# amp_soha.net
KiCad netlist of a schematic drawn in EAGLE
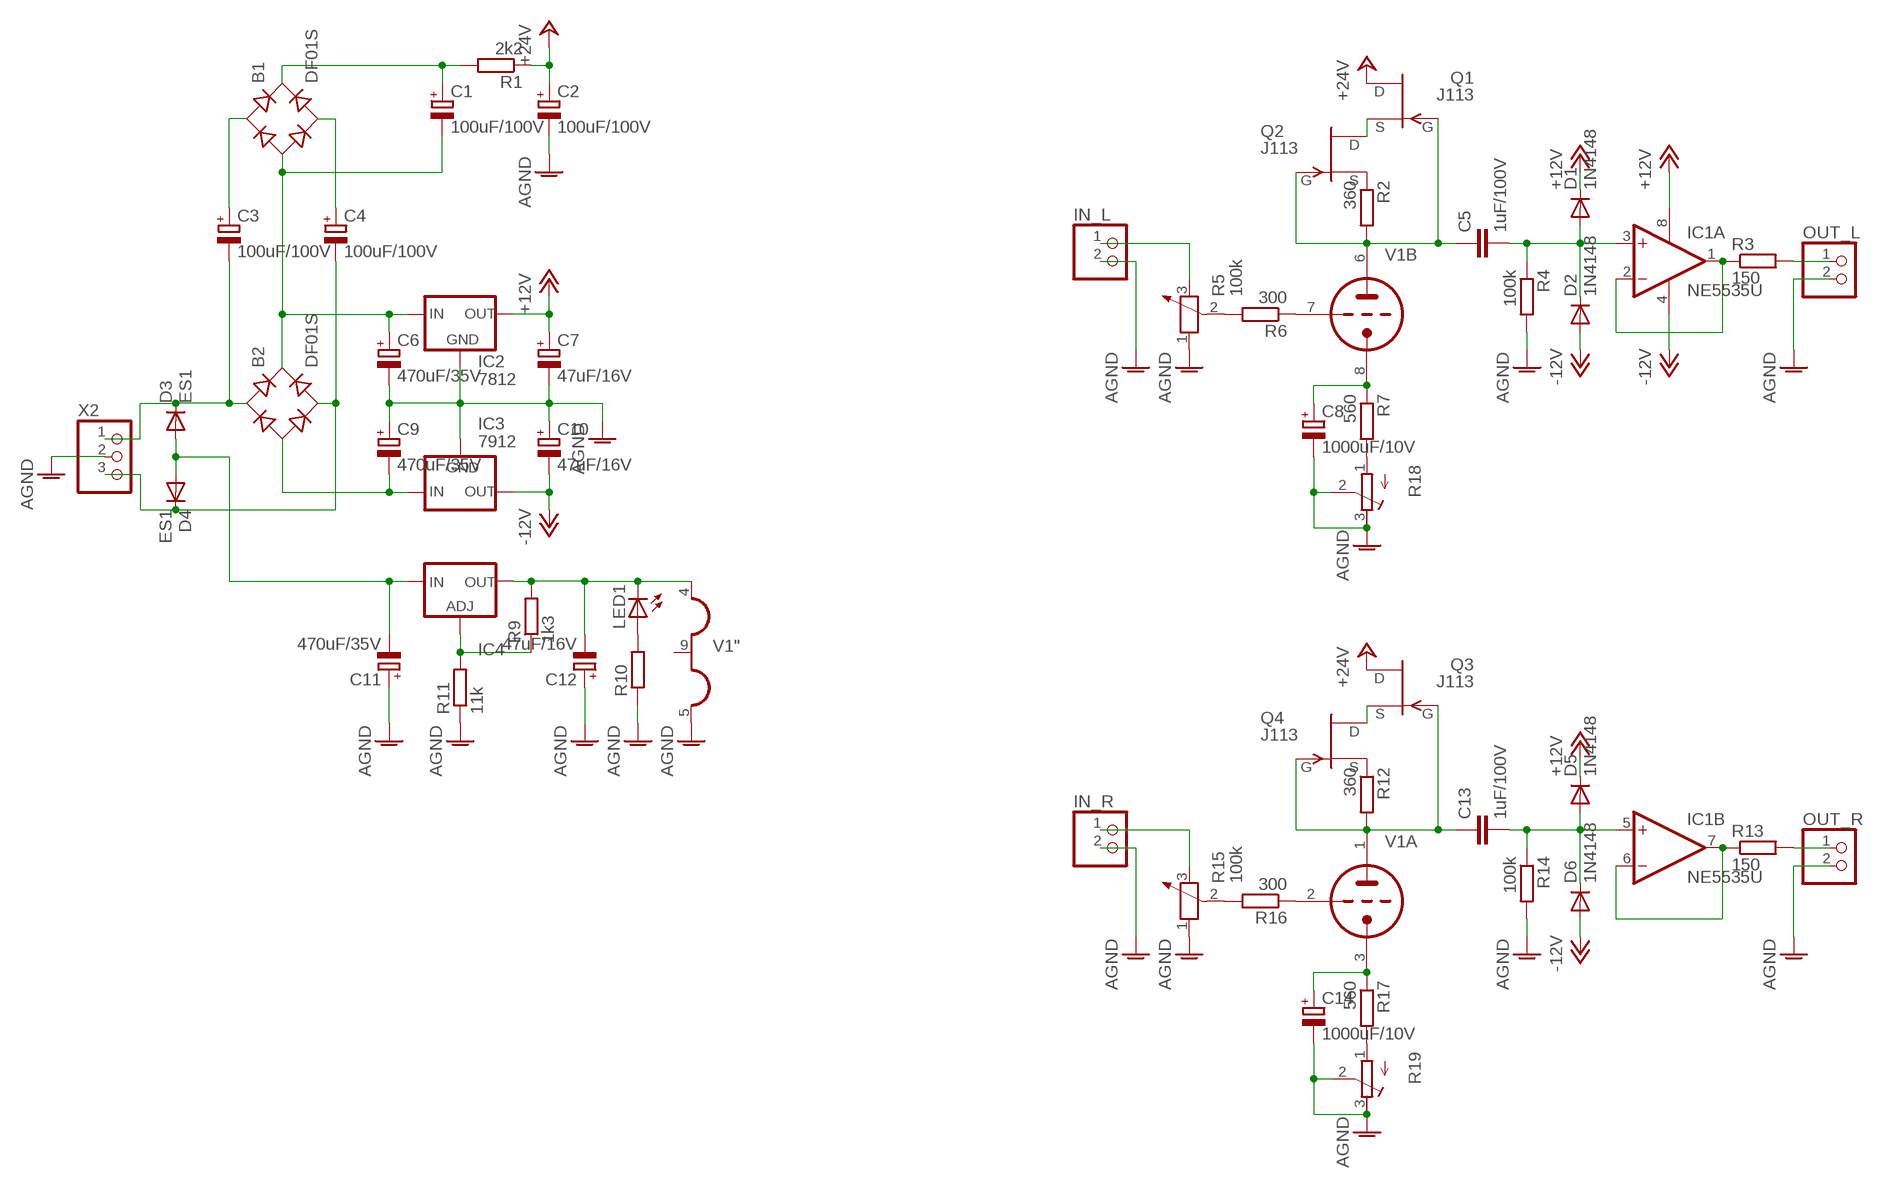
[diagram p0: schematic, sheet 1]

(export (version "E")
  (design (tool "Eeschema 10.0.6"))
  (components
    (comp (ref "B1")
      (value "DF01S")
      (footprint "eagle-import:DFS")
      (libsource (lib "eagle-import") (part "DFS01"))
    )
    (comp (ref "B2")
      (value "DF01S")
      (footprint "eagle-import:DFS")
      (libsource (lib "eagle-import") (part "DFS01"))
    )
    (comp (ref "C1")
      (value "100uF/100V")
      (footprint "eagle-import:E5-10,5")
      (libsource (lib "eagle-import") (part "CPOL-EUE5-10,5"))
    )
    (comp (ref "C2")
      (value "100uF/100V")
      (footprint "eagle-import:E5-10,5")
      (libsource (lib "eagle-import") (part "CPOL-EUE5-10,5"))
    )
    (comp (ref "C3")
      (value "100uF/100V")
      (footprint "eagle-import:E5-10,5")
      (libsource (lib "eagle-import") (part "CPOL-EUE5-10,5"))
    )
    (comp (ref "C4")
      (value "100uF/100V")
      (footprint "eagle-import:E5-10,5")
      (libsource (lib "eagle-import") (part "CPOL-EUE5-10,5"))
    )
    (comp (ref "C5")
      (value "1uF/100V")
      (footprint "eagle-import:C150-072X183")
      (libsource (lib "eagle-import") (part "C-EU150-072X183"))
    )
    (comp (ref "C6")
      (value "470uF/35V")
      (footprint "eagle-import:E5-10,5")
      (libsource (lib "eagle-import") (part "CPOL-EUE5-10,5"))
    )
    (comp (ref "C7")
      (value "47uF/16V")
      (footprint "eagle-import:E2,5-6")
      (libsource (lib "eagle-import") (part "CPOL-EUE2.5-6"))
    )
    (comp (ref "C8")
      (value "1000uF/10V")
      (footprint "eagle-import:E5-10,5")
      (libsource (lib "eagle-import") (part "CPOL-EUE5-10,5"))
    )
    (comp (ref "C9")
      (value "470uF/35V")
      (footprint "eagle-import:E5-10,5")
      (libsource (lib "eagle-import") (part "CPOL-EUE5-10,5"))
    )
    (comp (ref "C10")
      (value "47uF/16V")
      (footprint "eagle-import:E2,5-6")
      (libsource (lib "eagle-import") (part "CPOL-EUE2.5-6"))
    )
    (comp (ref "C11")
      (value "470uF/35V")
      (footprint "eagle-import:E5-10,5")
      (libsource (lib "eagle-import") (part "CPOL-EUE5-10,5"))
    )
    (comp (ref "C12")
      (value "47uF/16V")
      (footprint "eagle-import:E2,5-6")
      (libsource (lib "eagle-import") (part "CPOL-EUE2.5-6"))
    )
    (comp (ref "C13")
      (value "1uF/100V")
      (footprint "eagle-import:C150-072X183")
      (libsource (lib "eagle-import") (part "C-EU150-072X183"))
    )
    (comp (ref "C14")
      (value "1000uF/10V")
      (footprint "eagle-import:E5-10,5")
      (libsource (lib "eagle-import") (part "CPOL-EUE5-10,5"))
    )
    (comp (ref "D1")
      (value "1N4148")
      (footprint "eagle-import:D0805")
      (libsource (lib "eagle-import") (part "1N4148"))
    )
    (comp (ref "D2")
      (value "1N4148")
      (footprint "eagle-import:D0805")
      (libsource (lib "eagle-import") (part "1N4148"))
    )
    (comp (ref "D3")
      (value "ES1")
      (footprint "eagle-import:DO-214AC")
      (libsource (lib "eagle-import") (part "ES1"))
    )
    (comp (ref "D4")
      (value "ES1")
      (footprint "eagle-import:DO-214AC")
      (libsource (lib "eagle-import") (part "ES1"))
    )
    (comp (ref "D5")
      (value "1N4148")
      (footprint "eagle-import:D0805")
      (libsource (lib "eagle-import") (part "1N4148"))
    )
    (comp (ref "D6")
      (value "1N4148")
      (footprint "eagle-import:D0805")
      (libsource (lib "eagle-import") (part "1N4148"))
    )
    (comp (ref "IC1")
      (value "NE5535U")
      (footprint "eagle-import:SO08")
      (libsource (lib "eagle-import") (part "NE5535U"))
    )
    (comp (ref "IC2")
      (value "7812")
      (footprint "eagle-import:78XXS")
      (libsource (lib "eagle-import") (part "78XXTO-220"))
    )
    (comp (ref "IC3")
      (value "7912")
      (footprint "eagle-import:79XXS")
      (libsource (lib "eagle-import") (part "79XXTO-220"))
    )
    (comp (ref "IC4")
      (value "LM337TS")
      (footprint "eagle-import:337TS")
      (libsource (lib "eagle-import") (part "LM337TS"))
    )
    (comp (ref "IN_L")
      (value "PINHD-1X2")
      (footprint "eagle-import:1X02")
      (libsource (lib "eagle-import") (part "PINHD-1X2"))
    )
    (comp (ref "IN_R")
      (value "PINHD-1X2")
      (footprint "eagle-import:1X02")
      (libsource (lib "eagle-import") (part "PINHD-1X2"))
    )
    (comp (ref "LED1")
      (value "LED5MM")
      (footprint "eagle-import:LED5MM")
      (libsource (lib "eagle-import") (part "LED5MM"))
    )
    (comp (ref "OUT_L")
      (value "PINHD-1X2")
      (footprint "eagle-import:1X02")
      (libsource (lib "eagle-import") (part "PINHD-1X2"))
    )
    (comp (ref "OUT_R")
      (value "PINHD-1X2")
      (footprint "eagle-import:1X02")
      (libsource (lib "eagle-import") (part "PINHD-1X2"))
    )
    (comp (ref "Q1")
      (value "J113")
      (footprint "eagle-import:TO92")
      (libsource (lib "eagle-import") (part "J113"))
    )
    (comp (ref "Q2")
      (value "J113")
      (footprint "eagle-import:TO92")
      (libsource (lib "eagle-import") (part "J113"))
    )
    (comp (ref "Q3")
      (value "J113")
      (footprint "eagle-import:TO92")
      (libsource (lib "eagle-import") (part "J113"))
    )
    (comp (ref "Q4")
      (value "J113")
      (footprint "eagle-import:TO92")
      (libsource (lib "eagle-import") (part "J113"))
    )
    (comp (ref "R1")
      (value "2k2")
      (footprint "eagle-import:R0805")
      (libsource (lib "eagle-import") (part "R-EU_"))
    )
    (comp (ref "R2")
      (value "360")
      (footprint "eagle-import:R0805")
      (libsource (lib "eagle-import") (part "R-EU_"))
    )
    (comp (ref "R3")
      (value "150")
      (footprint "eagle-import:R0805")
      (libsource (lib "eagle-import") (part "R-EU_"))
    )
    (comp (ref "R4")
      (value "100k")
      (footprint "eagle-import:R0805")
      (libsource (lib "eagle-import") (part "R-EU_"))
    )
    (comp (ref "R5")
      (value "100k")
      (footprint "eagle-import:1X03")
      (libsource (lib "eagle-import") (part "POTENTIOMETER_"))
    )
    (comp (ref "R6")
      (value "300")
      (footprint "eagle-import:R0805")
      (libsource (lib "eagle-import") (part "R-EU_"))
    )
    (comp (ref "R7")
      (value "560")
      (footprint "eagle-import:R0805")
      (libsource (lib "eagle-import") (part "R-EU_"))
    )
    (comp (ref "R9")
      (value "1k3")
      (footprint "eagle-import:R0805")
      (libsource (lib "eagle-import") (part "R-EU_"))
    )
    (comp (ref "R10")
      (value "R-EU_")
      (footprint "eagle-import:R0805")
      (libsource (lib "eagle-import") (part "R-EU_"))
    )
    (comp (ref "R11")
      (value "11k")
      (footprint "eagle-import:R0805")
      (libsource (lib "eagle-import") (part "R-EU_"))
    )
    (comp (ref "R12")
      (value "360")
      (footprint "eagle-import:R0805")
      (libsource (lib "eagle-import") (part "R-EU_"))
    )
    (comp (ref "R13")
      (value "150")
      (footprint "eagle-import:R0805")
      (libsource (lib "eagle-import") (part "R-EU_"))
    )
    (comp (ref "R14")
      (value "100k")
      (footprint "eagle-import:R0805")
      (libsource (lib "eagle-import") (part "R-EU_"))
    )
    (comp (ref "R15")
      (value "100k")
      (footprint "eagle-import:1X03")
      (libsource (lib "eagle-import") (part "POTENTIOMETER_"))
    )
    (comp (ref "R16")
      (value "300")
      (footprint "eagle-import:R0805")
      (libsource (lib "eagle-import") (part "R-EU_"))
    )
    (comp (ref "R17")
      (value "560")
      (footprint "eagle-import:R0805")
      (libsource (lib "eagle-import") (part "R-EU_"))
    )
    (comp (ref "R18")
      (value "RTRIM329Y")
      (footprint "eagle-import:RTRIM3296Y")
      (libsource (lib "eagle-import") (part "RTRIM329Y"))
    )
    (comp (ref "R19")
      (value "RTRIM329Y")
      (footprint "eagle-import:RTRIM3296Y")
      (libsource (lib "eagle-import") (part "RTRIM329Y"))
    )
    (comp (ref "V1")
      (value "12AU7-P")
      (footprint "eagle-import:NOVAL")
      (libsource (lib "eagle-import") (part "12AU7-P"))
    )
    (comp (ref "X2")
      (value "W237-103")
      (footprint "eagle-import:W237-103")
      (libsource (lib "eagle-import") (part "W237-103"))
    )
  )
  (nets
    (net (code "1") (name "+12V") (class "Default")
      (node (ref "C7") (pin "+") (pinfunction "+_+") (pintype "passive"))
      (node (ref "D1") (pin "K") (pinfunction "C_K") (pintype "passive"))
      (node (ref "D5") (pin "K") (pinfunction "C_K") (pintype "passive"))
      (node (ref "IC1") (pin "8") (pinfunction "V+_8") (pintype "power_in"))
      (node (ref "IC2") (pin "OUT") (pinfunction "OUT_OUT") (pintype "passive"))
    )
    (net (code "2") (name "+24V") (class "Default")
      (node (ref "C2") (pin "+") (pinfunction "+_+") (pintype "passive"))
      (node (ref "Q1") (pin "3") (pinfunction "D_3") (pintype "passive"))
      (node (ref "Q3") (pin "3") (pinfunction "D_3") (pintype "passive"))
      (node (ref "R1") (pin "1") (pinfunction "1_1") (pintype "passive"))
    )
    (net (code "3") (name "-12V") (class "Default")
      (node (ref "C10") (pin "-") (pinfunction "-_-") (pintype "passive"))
      (node (ref "D2") (pin "A") (pinfunction "A_A") (pintype "passive"))
      (node (ref "D6") (pin "A") (pinfunction "A_A") (pintype "passive"))
      (node (ref "IC1") (pin "4") (pinfunction "V-_4") (pintype "power_in"))
      (node (ref "IC3") (pin "OUT") (pinfunction "OUT_OUT") (pintype "passive"))
    )
    (net (code "4") (name "AGND") (class "Default")
      (node (ref "C10") (pin "+") (pinfunction "+_+") (pintype "passive"))
      (node (ref "C11") (pin "+") (pinfunction "+_+") (pintype "passive"))
      (node (ref "C12") (pin "+") (pinfunction "+_+") (pintype "passive"))
      (node (ref "C14") (pin "-") (pinfunction "-_-") (pintype "passive"))
      (node (ref "C2") (pin "-") (pinfunction "-_-") (pintype "passive"))
      (node (ref "C6") (pin "-") (pinfunction "-_-") (pintype "passive"))
      (node (ref "C7") (pin "-") (pinfunction "-_-") (pintype "passive"))
      (node (ref "C8") (pin "-") (pinfunction "-_-") (pintype "passive"))
      (node (ref "C9") (pin "+") (pinfunction "+_+") (pintype "passive"))
      (node (ref "IC2") (pin "GND") (pinfunction "GND_GND") (pintype "input"))
      (node (ref "IC3") (pin "GND") (pinfunction "GND_GND") (pintype "input"))
      (node (ref "IN_L") (pin "2") (pinfunction "2_2") (pintype "passive"))
      (node (ref "IN_R") (pin "2") (pinfunction "2_2") (pintype "passive"))
      (node (ref "OUT_L") (pin "2") (pinfunction "2_2") (pintype "passive"))
      (node (ref "OUT_R") (pin "2") (pinfunction "2_2") (pintype "passive"))
      (node (ref "R10") (pin "1") (pinfunction "1_1") (pintype "passive"))
      (node (ref "R11") (pin "1") (pinfunction "1_1") (pintype "passive"))
      (node (ref "R14") (pin "2") (pinfunction "2_2") (pintype "passive"))
      (node (ref "R15") (pin "1") (pinfunction "1_1") (pintype "passive"))
      (node (ref "R18") (pin "2") (pinfunction "S_2") (pintype "passive"))
      (node (ref "R18") (pin "3") (pinfunction "E_3") (pintype "passive"))
      (node (ref "R19") (pin "2") (pinfunction "S_2") (pintype "passive"))
      (node (ref "R19") (pin "3") (pinfunction "E_3") (pintype "passive"))
      (node (ref "R4") (pin "2") (pinfunction "2_2") (pintype "passive"))
      (node (ref "R5") (pin "1") (pinfunction "1_1") (pintype "passive"))
      (node (ref "V1") (pin "5") (pinfunction "H3_5") (pintype "passive"))
      (node (ref "X2") (pin "2") (pinfunction "2_2") (pintype "passive"))
    )
    (net (code "5") (name "Net-(B1-Pad+)") (class "Default")
      (node (ref "B1") (pin "+") (pinfunction "+_+") (pintype "passive"))
      (node (ref "C1") (pin "+") (pinfunction "+_+") (pintype "passive"))
      (node (ref "R1") (pin "2") (pinfunction "2_2") (pintype "passive"))
    )
    (net (code "6") (name "Net-(B1-Pad-)") (class "Default")
      (node (ref "B1") (pin "-") (pinfunction "-_-") (pintype "passive"))
      (node (ref "B2") (pin "+") (pinfunction "+_+") (pintype "passive"))
      (node (ref "C1") (pin "-") (pinfunction "-_-") (pintype "passive"))
      (node (ref "C6") (pin "+") (pinfunction "+_+") (pintype "passive"))
      (node (ref "IC2") (pin "IN") (pinfunction "IN_IN") (pintype "input"))
    )
    (net (code "7") (name "Net-(B1-PadAC1)") (class "Default")
      (node (ref "B1") (pin "AC1") (pinfunction "AC1_AC1") (pintype "passive"))
      (node (ref "C3") (pin "+") (pinfunction "+_+") (pintype "passive"))
    )
    (net (code "8") (name "Net-(B1-PadAC2)") (class "Default")
      (node (ref "B1") (pin "AC2") (pinfunction "AC2_AC2") (pintype "passive"))
      (node (ref "C4") (pin "+") (pinfunction "+_+") (pintype "passive"))
    )
    (net (code "9") (name "Net-(B2-Pad-)") (class "Default")
      (node (ref "B2") (pin "-") (pinfunction "-_-") (pintype "passive"))
      (node (ref "C9") (pin "-") (pinfunction "-_-") (pintype "passive"))
      (node (ref "IC3") (pin "IN") (pinfunction "IN_IN") (pintype "input"))
    )
    (net (code "10") (name "Net-(B2-PadAC1)") (class "Default")
      (node (ref "B2") (pin "AC1") (pinfunction "AC1_AC1") (pintype "passive"))
      (node (ref "C3") (pin "-") (pinfunction "-_-") (pintype "passive"))
      (node (ref "D3") (pin "C") (pinfunction "C_C") (pintype "passive"))
      (node (ref "X2") (pin "1") (pinfunction "1_1") (pintype "passive"))
    )
    (net (code "11") (name "Net-(B2-PadAC2)") (class "Default")
      (node (ref "B2") (pin "AC2") (pinfunction "AC2_AC2") (pintype "passive"))
      (node (ref "C4") (pin "-") (pinfunction "-_-") (pintype "passive"))
      (node (ref "D4") (pin "C") (pinfunction "C_C") (pintype "passive"))
      (node (ref "X2") (pin "3") (pinfunction "3_3") (pintype "passive"))
    )
    (net (code "12") (name "Net-(D2-C)") (class "Default")
      (node (ref "C5") (pin "2") (pinfunction "2_2") (pintype "passive"))
      (node (ref "D1") (pin "A") (pinfunction "A_A") (pintype "passive"))
      (node (ref "D2") (pin "K") (pinfunction "C_K") (pintype "passive"))
      (node (ref "IC1") (pin "3") (pinfunction "+IN_3") (pintype "input"))
      (node (ref "R4") (pin "1") (pinfunction "1_1") (pintype "passive"))
    )
    (net (code "13") (name "Net-(D6-C)") (class "Default")
      (node (ref "C13") (pin "2") (pinfunction "2_2") (pintype "passive"))
      (node (ref "D5") (pin "A") (pinfunction "A_A") (pintype "passive"))
      (node (ref "D6") (pin "K") (pinfunction "C_K") (pintype "passive"))
      (node (ref "IC1") (pin "5") (pinfunction "+IN_5") (pintype "input"))
      (node (ref "R14") (pin "1") (pinfunction "1_1") (pintype "passive"))
    )
    (net (code "14") (name "Net-(IC1A--IN)") (class "Default")
      (node (ref "IC1") (pin "1") (pinfunction "OUT_1") (pintype "output"))
      (node (ref "IC1") (pin "2") (pinfunction "-IN_2") (pintype "input"))
      (node (ref "R3") (pin "1") (pinfunction "1_1") (pintype "passive"))
    )
    (net (code "15") (name "Net-(IC1B--IN)") (class "Default")
      (node (ref "IC1") (pin "6") (pinfunction "-IN_6") (pintype "input"))
      (node (ref "IC1") (pin "7") (pinfunction "OUT_7") (pintype "output"))
      (node (ref "R13") (pin "1") (pinfunction "1_1") (pintype "passive"))
    )
    (net (code "16") (name "Net-(IC4-ADJ)") (class "Default")
      (node (ref "IC4") (pin "1") (pinfunction "ADJ_1") (pintype "input"))
      (node (ref "R11") (pin "2") (pinfunction "2_2") (pintype "passive"))
      (node (ref "R9") (pin "1") (pinfunction "1_1") (pintype "passive"))
    )
    (net (code "17") (name "Net-(IC4-IN)") (class "Default")
      (node (ref "C11") (pin "-") (pinfunction "-_-") (pintype "passive"))
      (node (ref "D3") (pin "A") (pinfunction "A_A") (pintype "passive"))
      (node (ref "D4") (pin "A") (pinfunction "A_A") (pintype "passive"))
      (node (ref "IC4") (pin "2") (pinfunction "IN_2") (pintype "input"))
    )
    (net (code "18") (name "Net-(IC4-OUT)") (class "Default")
      (node (ref "C12") (pin "-") (pinfunction "-_-") (pintype "passive"))
      (node (ref "IC4") (pin "3") (pinfunction "OUT_3") (pintype "passive"))
      (node (ref "LED1") (pin "K") (pinfunction "C_K") (pintype "passive"))
      (node (ref "R9") (pin "2") (pinfunction "2_2") (pintype "passive"))
      (node (ref "V1") (pin "4") (pinfunction "H1_4") (pintype "passive"))
    )
    (net (code "19") (name "Net-(LED1-PadA)") (class "Default")
      (node (ref "LED1") (pin "A") (pinfunction "A_A") (pintype "passive"))
      (node (ref "R10") (pin "2") (pinfunction "2_2") (pintype "passive"))
    )
    (net (code "20") (name "Net-(OUT_L-Pad1)") (class "Default")
      (node (ref "OUT_L") (pin "1") (pinfunction "1_1") (pintype "passive"))
      (node (ref "R3") (pin "2") (pinfunction "2_2") (pintype "passive"))
    )
    (net (code "21") (name "Net-(OUT_R-Pad1)") (class "Default")
      (node (ref "OUT_R") (pin "1") (pinfunction "1_1") (pintype "passive"))
      (node (ref "R13") (pin "2") (pinfunction "2_2") (pintype "passive"))
    )
    (net (code "22") (name "Net-(Q1-G)") (class "Default")
      (node (ref "C5") (pin "1") (pinfunction "1_1") (pintype "passive"))
      (node (ref "Q1") (pin "1") (pinfunction "G_1") (pintype "passive"))
      (node (ref "Q2") (pin "1") (pinfunction "G_1") (pintype "passive"))
      (node (ref "R2") (pin "2") (pinfunction "2_2") (pintype "passive"))
      (node (ref "V1") (pin "6") (pinfunction "TA_6") (pintype "passive"))
    )
    (net (code "23") (name "Net-(Q1-S)") (class "Default")
      (node (ref "Q1") (pin "2") (pinfunction "S_2") (pintype "passive"))
      (node (ref "Q2") (pin "3") (pinfunction "D_3") (pintype "passive"))
    )
    (net (code "24") (name "Net-(Q2-S)") (class "Default")
      (node (ref "Q2") (pin "2") (pinfunction "S_2") (pintype "passive"))
      (node (ref "R2") (pin "1") (pinfunction "1_1") (pintype "passive"))
    )
    (net (code "25") (name "Net-(Q3-G)") (class "Default")
      (node (ref "C13") (pin "1") (pinfunction "1_1") (pintype "passive"))
      (node (ref "Q3") (pin "1") (pinfunction "G_1") (pintype "passive"))
      (node (ref "Q4") (pin "1") (pinfunction "G_1") (pintype "passive"))
      (node (ref "R12") (pin "2") (pinfunction "2_2") (pintype "passive"))
      (node (ref "V1") (pin "1") (pinfunction "TA_1") (pintype "passive"))
    )
    (net (code "26") (name "Net-(Q3-S)") (class "Default")
      (node (ref "Q3") (pin "2") (pinfunction "S_2") (pintype "passive"))
      (node (ref "Q4") (pin "3") (pinfunction "D_3") (pintype "passive"))
    )
    (net (code "27") (name "Net-(Q4-S)") (class "Default")
      (node (ref "Q4") (pin "2") (pinfunction "S_2") (pintype "passive"))
      (node (ref "R12") (pin "1") (pinfunction "1_1") (pintype "passive"))
    )
    (net (code "28") (name "Net-(R5-2)") (class "Default")
      (node (ref "IN_L") (pin "1") (pinfunction "1_1") (pintype "passive"))
      (node (ref "R5") (pin "3") (pinfunction "2_3") (pintype "passive"))
    )
    (net (code "29") (name "Net-(R5-3)") (class "Default")
      (node (ref "R5") (pin "2") (pinfunction "3_2") (pintype "passive"))
      (node (ref "R6") (pin "2") (pinfunction "2_2") (pintype "passive"))
    )
    (net (code "30") (name "Net-(R15-2)") (class "Default")
      (node (ref "IN_R") (pin "1") (pinfunction "1_1") (pintype "passive"))
      (node (ref "R15") (pin "3") (pinfunction "2_3") (pintype "passive"))
    )
    (net (code "31") (name "Net-(R15-3)") (class "Default")
      (node (ref "R15") (pin "2") (pinfunction "3_2") (pintype "passive"))
      (node (ref "R16") (pin "2") (pinfunction "2_2") (pintype "passive"))
    )
    (net (code "32") (name "Net-(R18-A)") (class "Default")
      (node (ref "R18") (pin "1") (pinfunction "A_1") (pintype "passive"))
      (node (ref "R7") (pin "2") (pinfunction "2_2") (pintype "passive"))
    )
    (net (code "33") (name "Net-(R19-A)") (class "Default")
      (node (ref "R17") (pin "2") (pinfunction "2_2") (pintype "passive"))
      (node (ref "R19") (pin "1") (pinfunction "A_1") (pintype "passive"))
    )
    (net (code "34") (name "Net-(V1B-TG)") (class "Default")
      (node (ref "R16") (pin "1") (pinfunction "1_1") (pintype "passive"))
      (node (ref "V1") (pin "2") (pinfunction "TG_2") (pintype "passive"))
    )
    (net (code "35") (name "Net-(V1B-TK)") (class "Default")
      (node (ref "C14") (pin "+") (pinfunction "+_+") (pintype "passive"))
      (node (ref "R17") (pin "1") (pinfunction "1_1") (pintype "passive"))
      (node (ref "V1") (pin "3") (pinfunction "TK_3") (pintype "passive"))
    )
    (net (code "36") (name "Net-(V1C-TG)") (class "Default")
      (node (ref "R6") (pin "1") (pinfunction "1_1") (pintype "passive"))
      (node (ref "V1") (pin "7") (pinfunction "TG_7") (pintype "passive"))
    )
    (net (code "37") (name "Net-(V1C-TK)") (class "Default")
      (node (ref "C8") (pin "+") (pinfunction "+_+") (pintype "passive"))
      (node (ref "R7") (pin "1") (pinfunction "1_1") (pintype "passive"))
      (node (ref "V1") (pin "8") (pinfunction "TK_8") (pintype "passive"))
    )
    (net (code "38") (name "unconnected-(V1A-H2-Pad9)") (class "Default")
      (node (ref "V1") (pin "9") (pinfunction "H2_9") (pintype "passive"))
    )
  )
)
